# Sheet2.net
KiCad netlist of a schematic drawn in Altium Designer
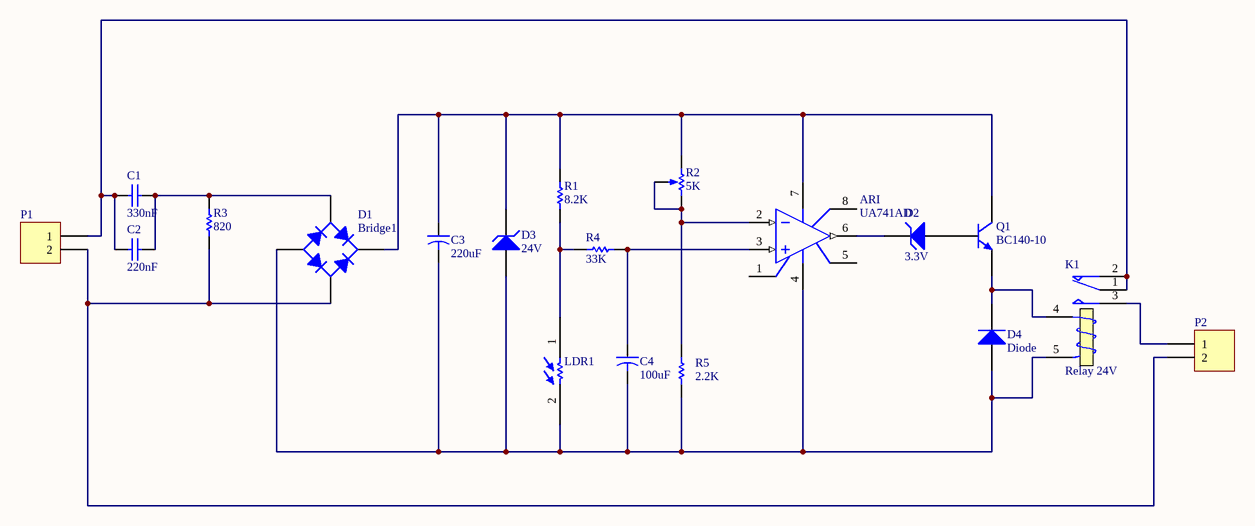
[diagram p0: Sheet2.SchDoc]

(export (version "E")
  (design (tool "Eeschema 10.0.6"))
  (components
    (comp (ref "ARI")
      (value "UA741AD")
      (footprint "UA741cp")
      (description "General-Purpose Single Operational Amplifier")
      (fields (field (name "PUBLISHER") "Altium Limited"))
      (libsource (lib "altium-import") (part "root_0_UA741AD_"))
    )
    (comp (ref "C1")
      (value "330nF")
      (footprint "220nfcap_330nfcap")
      (description "Capacitor")
      (fields (field (name "PUBLISHER") "Altium Limited"))
      (libsource (lib "Miscellaneous Devices") (part "Cap"))
    )
    (comp (ref "C2")
      (value "220nF")
      (footprint "220nfcap_330nfcap")
      (description "Capacitor")
      (fields (field (name "PUBLISHER") "Altium Limited"))
      (libsource (lib "Miscellaneous Devices") (part "Cap"))
    )
    (comp (ref "C3")
      (value "220uF")
      (footprint "cap220uf_electerolytic")
      (description "Capacitor")
      (fields (field (name "PUBLISHER") "Altium Limited"))
      (libsource (lib "Miscellaneous Devices") (part "Cap2"))
    )
    (comp (ref "C4")
      (value "100uF")
      (footprint "CAP100uF_ELECTROLYTIC")
      (description "Capacitor")
      (fields (field (name "PUBLISHER") "Altium Limited"))
      (libsource (lib "Miscellaneous Devices") (part "Cap2"))
    )
    (comp (ref "D1")
      (value "Bridge1")
      (footprint "diode_bridge")
      (description "Full Wave Diode Bridge")
      (fields (field (name "PUBLISHER") "Altium Limited"))
      (libsource (lib "Miscellaneous Devices") (part "Bridge1"))
    )
    (comp (ref "D2")
      (value "3.3V")
      (footprint "zener_diode")
      (description "Zener Diode")
      (fields (field (name "PUBLISHER") "Altium Limited"))
      (libsource (lib "Miscellaneous Devices") (part "D Zener"))
    )
    (comp (ref "D3")
      (value "24V")
      (footprint "zener_diode")
      (description "Zener Diode")
      (fields (field (name "PUBLISHER") "Altium Limited"))
      (libsource (lib "Miscellaneous Devices") (part "D Zener"))
    )
    (comp (ref "D4")
      (value "Diode")
      (footprint "diode")
      (description "Default Diode")
      (fields (field (name "PUBLISHER") "Altium Limited"))
      (libsource (lib "Miscellaneous Devices") (part "Diode"))
    )
    (comp (ref "K1")
      (value "Relay 24V")
      (footprint "Relay")
      (description "SPDT Relay")
      (fields (field (name "PUBLISHER") "Altium Limited"))
      (libsource (lib "Miscellaneous Devices") (part "Relay"))
    )
    (comp (ref "LDR1") (value "~") (footprint "LDR") (libsource (lib "Schlib2") (part "LDR")))
    (comp (ref "P1")
      (value "Header 2")
      (footprint "Connector")
      (description "Header, 2-Pin")
      (fields (field (name "PUBLISHER") "Altium Limited"))
      (libsource (lib "Miscellaneous Connectors") (part "Header 2"))
    )
    (comp (ref "P2")
      (value "Header 2")
      (footprint "Connector")
      (description "Header, 2-Pin")
      (fields (field (name "PUBLISHER") "Altium Limited"))
      (libsource (lib "") (part "Header 2_1"))
    )
    (comp (ref "Q1")
      (value "BC140-10")
      (footprint "Bipolar_Transistors")
      (description "Amplifier Transistor NPN Silicon")
      (fields (field (name "PUBLISHER") "Altium Limited"))
      (libsource (lib "Motorola Discrete BJT") (part "BC140-10"))
    )
    (comp (ref "R1")
      (value "8.2K")
      (footprint "Res_filmcarbon")
      (description "Resistor")
      (fields (field (name "PUBLISHER") "Altium Limited"))
      (libsource (lib "Miscellaneous Devices") (part "Res1"))
    )
    (comp (ref "R2")
      (value "5K")
      (footprint "potentiometer")
      (description "Potentiometer")
      (fields (field (name "PUBLISHER") "Altium Limited"))
      (libsource (lib "Miscellaneous Devices") (part "RPot"))
    )
    (comp (ref "R3")
      (value "820")
      (footprint "Res_filmcarbon")
      (description "Resistor")
      (fields (field (name "PUBLISHER") "Altium Limited"))
      (libsource (lib "Miscellaneous Devices") (part "Res1"))
    )
    (comp (ref "R4")
      (value "33K")
      (footprint "Res_filmcarbon")
      (description "Resistor")
      (fields (field (name "PUBLISHER") "Altium Limited"))
      (libsource (lib "Miscellaneous Devices") (part "Res1"))
    )
    (comp (ref "R5")
      (value "2.2K")
      (footprint "Res_filmcarbon")
      (description "Resistor")
      (fields (field (name "PUBLISHER") "Altium Limited"))
      (libsource (lib "Miscellaneous Devices") (part "Res1"))
    )
  )
  (nets
    (net (code "1") (name "Net-(ARI-IN+)") (class "Default")
      (node (ref "ARI") (pin "3") (pinfunction "IN+_3") (pintype "input"))
      (node (ref "C4") (pin "1") (pinfunction "1_1") (pintype "passive"))
      (node (ref "R4") (pin "2") (pinfunction "2_2") (pintype "passive"))
    )
    (net (code "2") (name "Net-(ARI-IN-)") (class "Default")
      (node (ref "ARI") (pin "2") (pinfunction "IN-_2") (pintype "input"))
      (node (ref "R2") (pin "2") (pinfunction "BOT_2") (pintype "passive"))
      (node (ref "R2") (pin "3") (pinfunction "TAP_3") (pintype "passive"))
      (node (ref "R5") (pin "2") (pinfunction "2_2") (pintype "passive"))
    )
    (net (code "3") (name "Net-(ARI-OUT)") (class "Default")
      (node (ref "ARI") (pin "6") (pinfunction "OUT_6") (pintype "output"))
      (node (ref "D2") (pin "2") (pinfunction "K_2") (pintype "passive"))
    )
    (net (code "4") (name "Net-(ARI-V+)") (class "Default")
      (node (ref "ARI") (pin "7") (pinfunction "V+_7") (pintype "power_in"))
      (node (ref "C3") (pin "1") (pinfunction "1_1") (pintype "passive"))
      (node (ref "D1") (pin "1") (pinfunction "K_1") (pintype "passive"))
      (node (ref "D3") (pin "2") (pinfunction "K_2") (pintype "passive"))
      (node (ref "Q1") (pin "3") (pinfunction "C_3") (pintype "passive"))
      (node (ref "R1") (pin "2") (pinfunction "2_2") (pintype "passive"))
      (node (ref "R2") (pin "1") (pinfunction "TOP_1") (pintype "passive"))
    )
    (net (code "5") (name "Net-(ARI-V-)") (class "Default")
      (node (ref "ARI") (pin "4") (pinfunction "V-_4") (pintype "power_in"))
      (node (ref "C3") (pin "2") (pinfunction "2_2") (pintype "passive"))
      (node (ref "C4") (pin "2") (pinfunction "2_2") (pintype "passive"))
      (node (ref "D1") (pin "3") (pinfunction "A_3") (pintype "passive"))
      (node (ref "D3") (pin "1") (pinfunction "A_1") (pintype "passive"))
      (node (ref "D4") (pin "1") (pinfunction "A_1") (pintype "passive"))
      (node (ref "K1") (pin "5") (pinfunction "T2_5") (pintype "passive"))
      (node (ref "LDR1") (pin "2") (pintype "passive"))
      (node (ref "R5") (pin "1") (pinfunction "1_1") (pintype "passive"))
    )
    (net (code "6") (name "Net-(C1-Pad2)") (class "Default")
      (node (ref "C1") (pin "2") (pinfunction "2_2") (pintype "passive"))
      (node (ref "C2") (pin "2") (pinfunction "2_2") (pintype "passive"))
      (node (ref "D1") (pin "4") (pinfunction "C_4") (pintype "passive"))
      (node (ref "R3") (pin "2") (pinfunction "2_2") (pintype "passive"))
    )
    (net (code "7") (name "Net-(D1-C-Pad2)") (class "Default")
      (node (ref "D1") (pin "2") (pinfunction "C_2") (pintype "passive"))
      (node (ref "P1") (pin "2") (pinfunction "2_2") (pintype "passive"))
      (node (ref "P2") (pin "2") (pinfunction "2_2") (pintype "passive"))
      (node (ref "R3") (pin "1") (pinfunction "1_1") (pintype "passive"))
    )
    (net (code "8") (name "Net-(D2-A)") (class "Default")
      (node (ref "D2") (pin "1") (pinfunction "A_1") (pintype "passive"))
      (node (ref "Q1") (pin "2") (pinfunction "B_2") (pintype "passive"))
    )
    (net (code "9") (name "Net-(D4-K)") (class "Default")
      (node (ref "D4") (pin "2") (pinfunction "K_2") (pintype "passive"))
      (node (ref "K1") (pin "4") (pinfunction "T1_4") (pintype "passive"))
      (node (ref "Q1") (pin "1") (pinfunction "E_1") (pintype "passive"))
    )
    (net (code "10") (name "Net-(K1-COM)") (class "Default")
      (node (ref "C1") (pin "1") (pinfunction "1_1") (pintype "passive"))
      (node (ref "C2") (pin "1") (pinfunction "1_1") (pintype "passive"))
      (node (ref "K1") (pin "1") (pinfunction "COM_1") (pintype "passive"))
      (node (ref "K1") (pin "2") (pinfunction "NC_2") (pintype "passive"))
      (node (ref "P1") (pin "1") (pinfunction "1_1") (pintype "passive"))
    )
    (net (code "11") (name "Net-(K1-NO)") (class "Default")
      (node (ref "K1") (pin "3") (pinfunction "NO_3") (pintype "passive"))
      (node (ref "P2") (pin "1") (pinfunction "1_1") (pintype "passive"))
    )
    (net (code "12") (name "Net-(LDR1-Pad1)") (class "Default")
      (node (ref "LDR1") (pin "1") (pintype "passive"))
      (node (ref "R1") (pin "1") (pinfunction "1_1") (pintype "passive"))
      (node (ref "R4") (pin "1") (pinfunction "1_1") (pintype "passive"))
    )
    (net (code "13") (name "unconnected-(ARI-NC-Pad8)") (class "Default")
      (node (ref "ARI") (pin "8") (pinfunction "NC_8") (pintype "passive"))
    )
    (net (code "14") (name "unconnected-(ARI-OS_NULL-Pad1)") (class "Default")
      (node (ref "ARI") (pin "1") (pinfunction "OS_NULL_1") (pintype "passive"))
    )
    (net (code "15") (name "unconnected-(ARI-OS_NULL-Pad5)") (class "Default")
      (node (ref "ARI") (pin "5") (pinfunction "OS_NULL_5") (pintype "passive"))
    )
  )
)
